# fet_high_side_switch.net
KiCad netlist of a schematic drawn in EAGLE
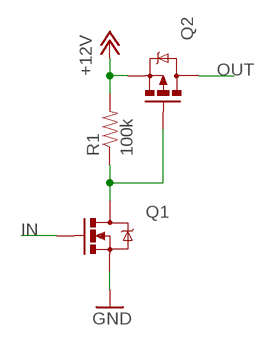
[diagram p0: schematic, sheet 1]

(export (version "E")
  (design (tool "Eeschema 10.0.6"))
  (components
    (comp (ref "Q1")
      (value "MOSFET-NCHANNEL2N7000")
      (footprint "eagle-import:TO-92")
      (libsource (lib "eagle-import") (part "MOSFET-NCHANNEL2N7000"))
    )
    (comp (ref "Q2")
      (value "MOSFET-PCHANNELSMD")
      (footprint "eagle-import:SOT23-3")
      (libsource (lib "eagle-import") (part "MOSFET-PCHANNELSMD"))
    )
    (comp (ref "R1")
      (value "100k")
      (footprint "eagle-import:0402-RES")
      (libsource (lib "eagle-import") (part "RESISTOR0402-RES"))
    )
  )
  (nets
    (net (code "1") (name "+12V") (class "Default")
      (node (ref "Q2") (pin "2") (pinfunction "S_2") (pintype "passive"))
      (node (ref "R1") (pin "2") (pinfunction "2_2") (pintype "passive"))
    )
    (net (code "2") (name "/IN") (class "Default")
      (node (ref "Q1") (pin "2") (pinfunction "G_2") (pintype "passive"))
    )
    (net (code "3") (name "/OUT") (class "Default")
      (node (ref "Q2") (pin "3") (pinfunction "D_3") (pintype "passive"))
    )
    (net (code "4") (name "GND") (class "Default")
      (node (ref "Q1") (pin "1") (pinfunction "S_1") (pintype "passive"))
    )
    (net (code "5") (name "Net-(Q1-D)") (class "Default")
      (node (ref "Q1") (pin "3") (pinfunction "D_3") (pintype "passive"))
      (node (ref "Q2") (pin "1") (pinfunction "G_1") (pintype "passive"))
      (node (ref "R1") (pin "1") (pinfunction "1_1") (pintype "passive"))
    )
  )
)
